# SCH_New_Project_2022-11-03.net
KiCad netlist of a schematic drawn in EasyEDA
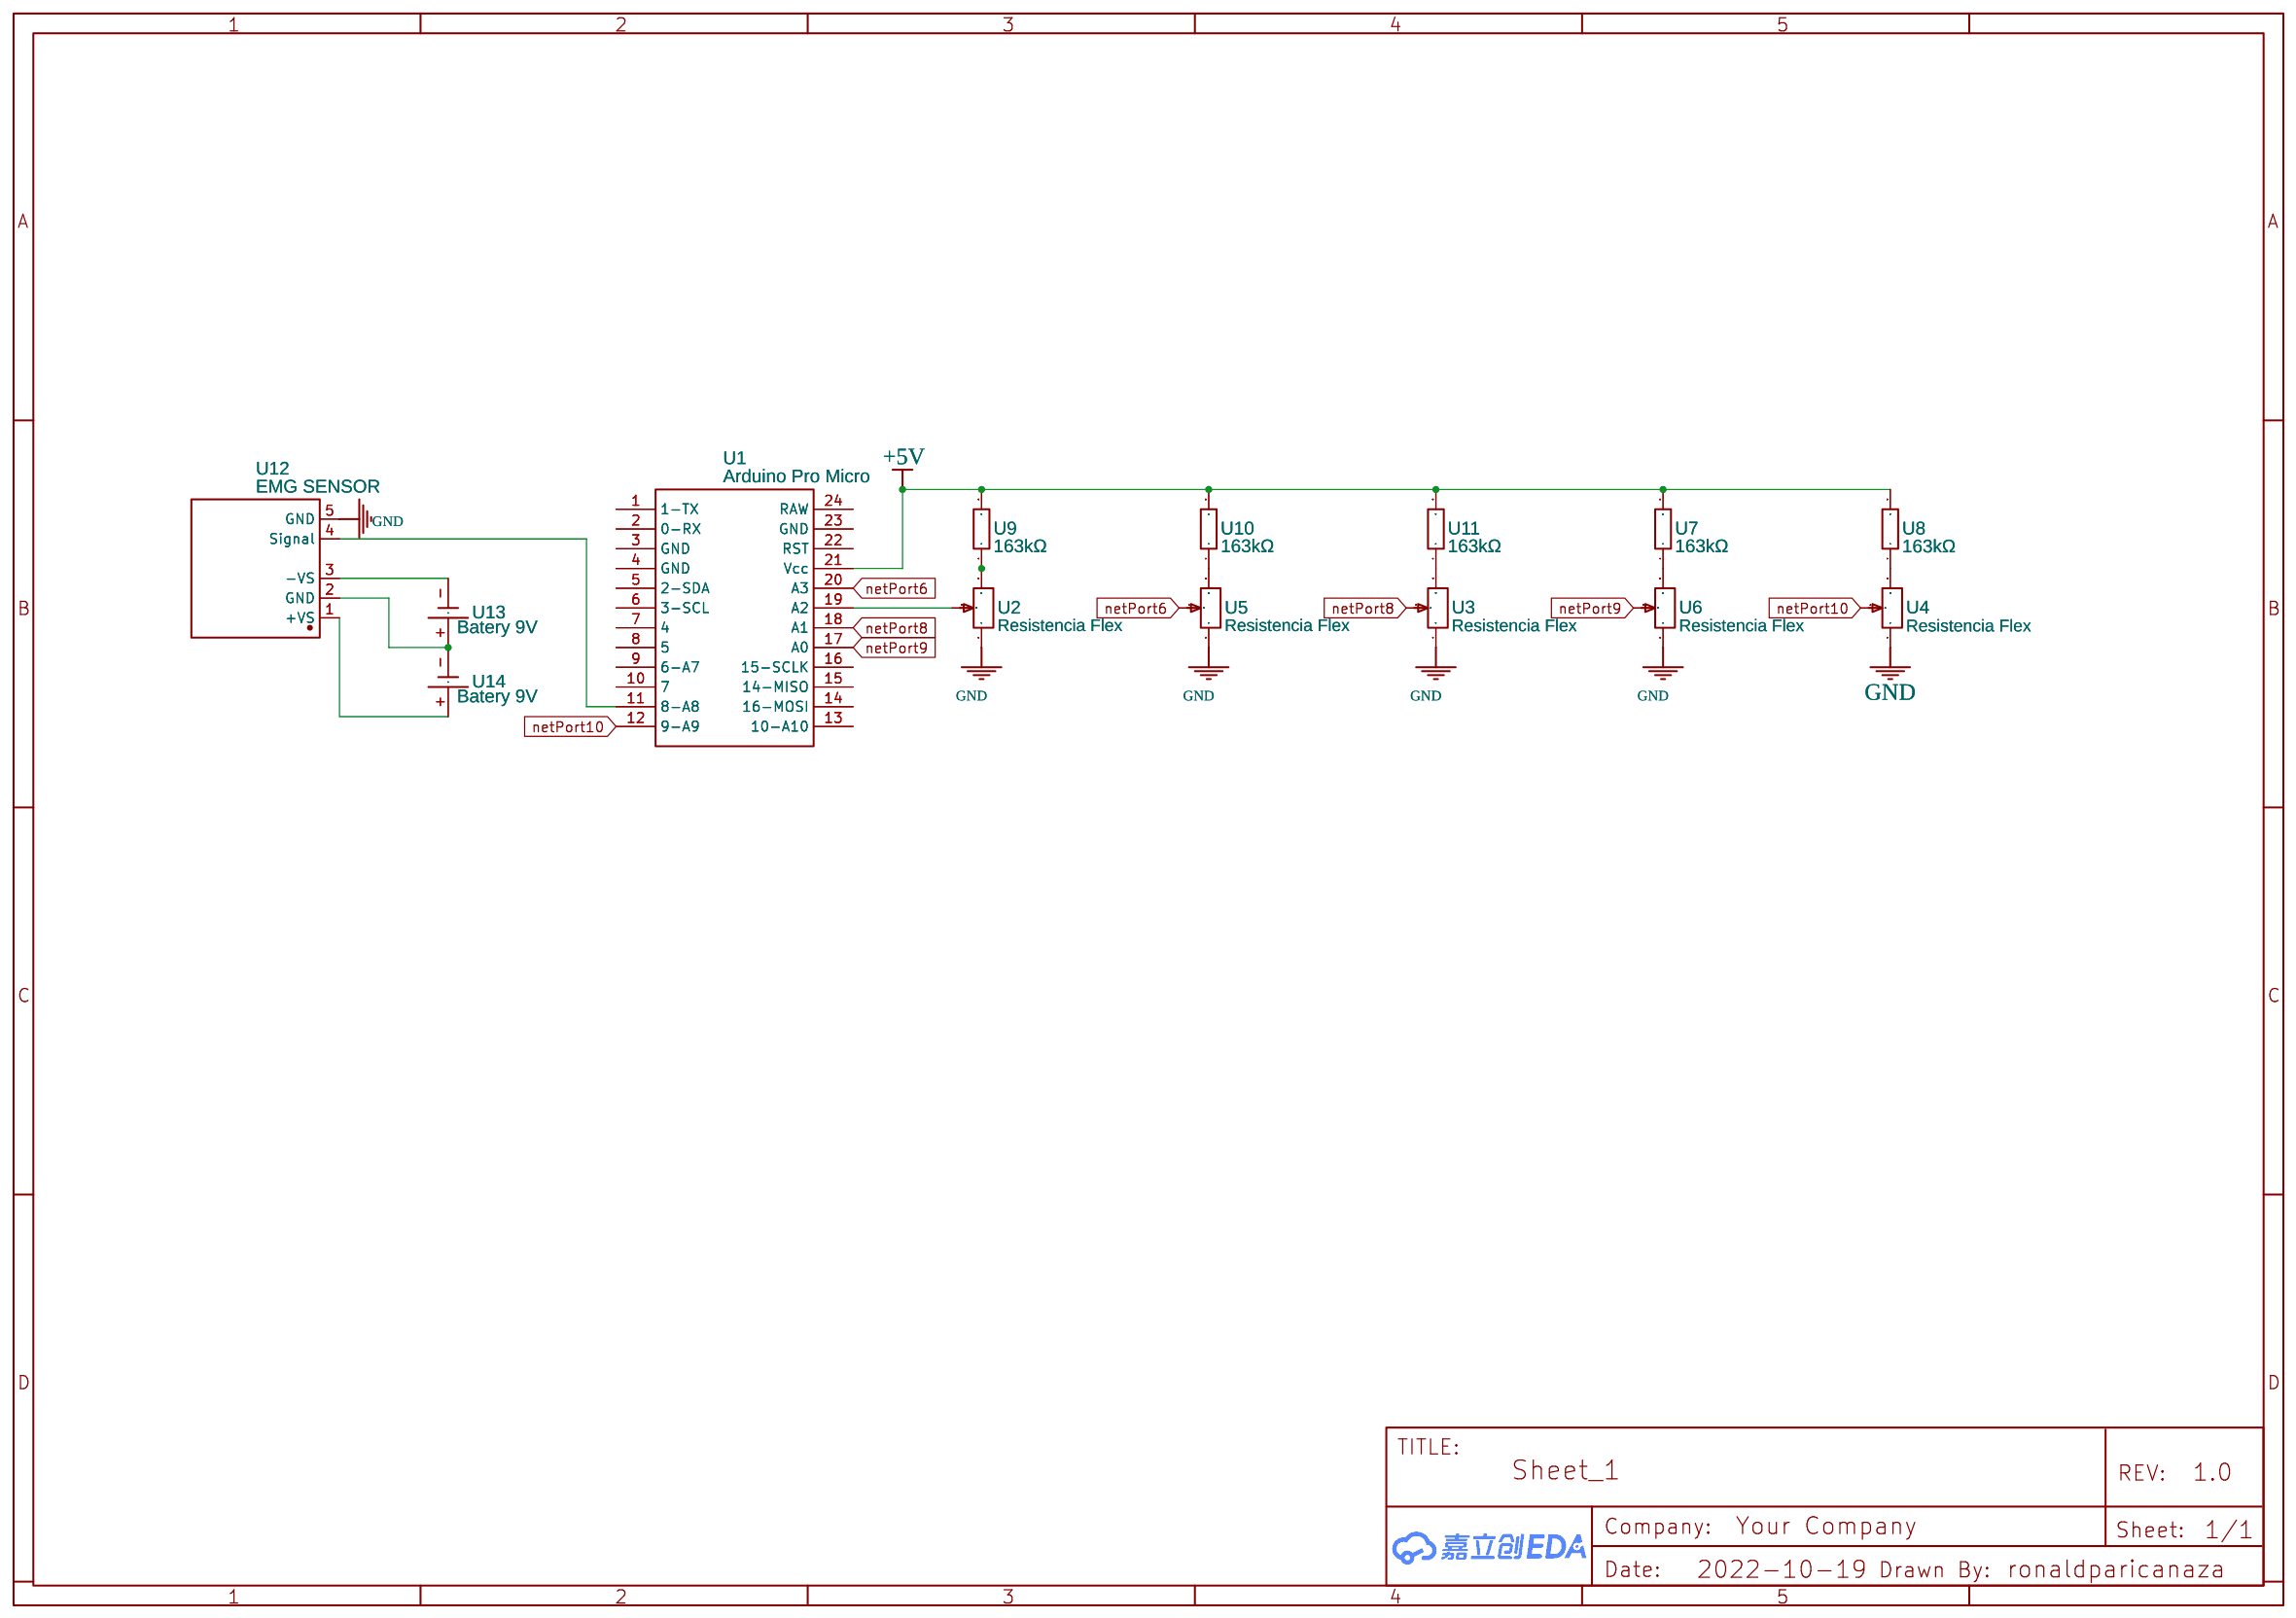
[diagram p0: schematic sheet]

(export (version "E")
  (design (tool "Eeschema 10.0.6"))
  (components
    (comp (ref "U1") (value "Arduino Pro Micro") (libsource (lib "") (part "Arduino Pro Micro")))
    (comp (ref "U2")
      (value "Resistencia Flex")
      (fields
        (field (name "BOM_Manufacturer Part") "3*3Potentiometer-10kΩ20%")
        (field (name "BOM_Supplier Part") "C9900010776")
      )
      (libsource (lib "") (part "3*3POTENTIOMETER-10KΩ20%"))
    )
    (comp (ref "U3")
      (value "Resistencia Flex")
      (fields
        (field (name "BOM_Manufacturer Part") "3*3Potentiometer-10kΩ20%")
        (field (name "BOM_Supplier Part") "C9900010776")
      )
      (libsource (lib "") (part "3*3POTENTIOMETER-10KΩ20%"))
    )
    (comp (ref "U4")
      (value "Resistencia Flex")
      (fields
        (field (name "BOM_Manufacturer Part") "3*3Potentiometer-10kΩ20%")
        (field (name "BOM_Supplier Part") "C9900010776")
      )
      (libsource (lib "") (part "3*3POTENTIOMETER-10KΩ20%"))
    )
    (comp (ref "U5")
      (value "Resistencia Flex")
      (fields
        (field (name "BOM_Manufacturer Part") "3*3Potentiometer-10kΩ20%")
        (field (name "BOM_Supplier Part") "C9900010776")
      )
      (libsource (lib "") (part "3*3POTENTIOMETER-10KΩ20%"))
    )
    (comp (ref "U6")
      (value "Resistencia Flex")
      (fields
        (field (name "BOM_Manufacturer Part") "3*3Potentiometer-10kΩ20%")
        (field (name "BOM_Supplier Part") "C9900010776")
      )
      (libsource (lib "") (part "3*3POTENTIOMETER-10KΩ20%"))
    )
    (comp (ref "U7")
      (value "163kΩ")
      (fields
        (field (name "BOM_Manufacturer Part") "HPCR0402F475KK9")
        (field (name "BOM_Supplier Part") "C365017")
      )
      (libsource (lib "") (part "HPCR0402F475KK9"))
    )
    (comp (ref "U8")
      (value "163kΩ")
      (fields
        (field (name "BOM_Manufacturer Part") "HPCR0402F475KK9")
        (field (name "BOM_Supplier Part") "C365017")
      )
      (libsource (lib "") (part "HPCR0402F475KK9"))
    )
    (comp (ref "U9")
      (value "163kΩ")
      (fields
        (field (name "BOM_Manufacturer Part") "HPCR0402F475KK9")
        (field (name "BOM_Supplier Part") "C365017")
      )
      (libsource (lib "") (part "HPCR0402F475KK9"))
    )
    (comp (ref "U10")
      (value "163kΩ")
      (fields
        (field (name "BOM_Manufacturer Part") "HPCR0402F475KK9")
        (field (name "BOM_Supplier Part") "C365017")
      )
      (libsource (lib "") (part "HPCR0402F475KK9"))
    )
    (comp (ref "U11")
      (value "163kΩ")
      (fields
        (field (name "BOM_Manufacturer Part") "HPCR0402F475KK9")
        (field (name "BOM_Supplier Part") "C365017")
      )
      (libsource (lib "") (part "HPCR0402F475KK9"))
    )
    (comp (ref "U12") (value "EMG SENSOR") (libsource (lib "") (part "EMG SENSOR")))
    (comp (ref "U13") (value "Batery 9V") (libsource (lib "") (part "Batery")))
    (comp (ref "U14") (value "Batery 9V") (libsource (lib "") (part "Batery")))
  )
  (nets
    (net (code "1") (name "+5V") (class "Default")
      (node (ref "U1") (pin "21") (pinfunction "Vcc_21") (pintype "unspecified"))
      (node (ref "U10") (pin "2") (pinfunction "2_2") (pintype "unspecified"))
      (node (ref "U11") (pin "2") (pinfunction "2_2") (pintype "unspecified"))
      (node (ref "U7") (pin "2") (pinfunction "2_2") (pintype "unspecified"))
      (node (ref "U8") (pin "2") (pinfunction "2_2") (pintype "unspecified"))
      (node (ref "U9") (pin "2") (pinfunction "2_2") (pintype "unspecified"))
    )
    (net (code "2") (name "GND") (class "Default")
      (node (ref "U12") (pin "5") (pinfunction "GND_5") (pintype "unspecified"))
      (node (ref "U2") (pin "1") (pinfunction "1_1") (pintype "input"))
      (node (ref "U3") (pin "1") (pinfunction "1_1") (pintype "input"))
      (node (ref "U4") (pin "1") (pinfunction "1_1") (pintype "input"))
      (node (ref "U5") (pin "1") (pinfunction "1_1") (pintype "input"))
      (node (ref "U6") (pin "1") (pinfunction "1_1") (pintype "input"))
    )
    (net (code "3") (name "Net-(U1-8-A8)") (class "Default")
      (node (ref "U1") (pin "11") (pinfunction "8-A8_11") (pintype "unspecified"))
      (node (ref "U12") (pin "4") (pinfunction "Signal_4") (pintype "unspecified"))
    )
    (net (code "4") (name "Net-(U1-A2)") (class "Default")
      (node (ref "U1") (pin "19") (pinfunction "A2_19") (pintype "unspecified"))
      (node (ref "U2") (pin "2") (pinfunction "2_2") (pintype "input"))
    )
    (net (code "5") (name "Net-(U2-Pad3)") (class "Default")
      (node (ref "U2") (pin "3") (pinfunction "3_3") (pintype "input"))
      (node (ref "U9") (pin "1") (pinfunction "1_1") (pintype "unspecified"))
    )
    (net (code "6") (name "Net-(U4-Pad3)") (class "Default")
      (node (ref "U4") (pin "3") (pinfunction "3_3") (pintype "input"))
      (node (ref "U8") (pin "1") (pinfunction "1_1") (pintype "unspecified"))
    )
    (net (code "7") (name "Net-(U6-Pad3)") (class "Default")
      (node (ref "U6") (pin "3") (pinfunction "3_3") (pintype "input"))
      (node (ref "U7") (pin "1") (pinfunction "1_1") (pintype "unspecified"))
    )
    (net (code "8") (name "Net-(U10-Pad1)") (class "Default")
      (node (ref "U10") (pin "1") (pinfunction "1_1") (pintype "unspecified"))
      (node (ref "U5") (pin "3") (pinfunction "3_3") (pintype "input"))
    )
    (net (code "9") (name "Net-(U11-Pad1)") (class "Default")
      (node (ref "U11") (pin "1") (pinfunction "1_1") (pintype "unspecified"))
      (node (ref "U3") (pin "3") (pinfunction "3_3") (pintype "input"))
    )
    (net (code "10") (name "Net-(U12-+VS)") (class "Default")
      (node (ref "U12") (pin "1") (pinfunction "+VS_1") (pintype "unspecified"))
      (node (ref "U14") (pin "+") (pinfunction "+_+") (pintype "unspecified"))
    )
    (net (code "11") (name "Net-(U12--VS)") (class "Default")
      (node (ref "U12") (pin "3") (pinfunction "-VS_3") (pintype "unspecified"))
      (node (ref "U13") (pin "-") (pinfunction "-_-") (pintype "unspecified"))
    )
    (net (code "12") (name "Net-(U12-GND-Pad2)") (class "Default")
      (node (ref "U12") (pin "2") (pinfunction "GND_2") (pintype "unspecified"))
      (node (ref "U13") (pin "+") (pinfunction "+_+") (pintype "unspecified"))
      (node (ref "U14") (pin "-") (pinfunction "-_-") (pintype "unspecified"))
    )
    (net (code "13") (name "netPort6") (class "Default")
      (node (ref "U1") (pin "20") (pinfunction "A3_20") (pintype "unspecified"))
      (node (ref "U5") (pin "2") (pinfunction "2_2") (pintype "input"))
    )
    (net (code "14") (name "netPort8") (class "Default")
      (node (ref "U1") (pin "18") (pinfunction "A1_18") (pintype "unspecified"))
      (node (ref "U3") (pin "2") (pinfunction "2_2") (pintype "input"))
    )
    (net (code "15") (name "netPort9") (class "Default")
      (node (ref "U1") (pin "17") (pinfunction "A0_17") (pintype "unspecified"))
      (node (ref "U6") (pin "2") (pinfunction "2_2") (pintype "input"))
    )
    (net (code "16") (name "netPort10") (class "Default")
      (node (ref "U1") (pin "12") (pinfunction "9-A9_12") (pintype "unspecified"))
      (node (ref "U4") (pin "2") (pinfunction "2_2") (pintype "input"))
    )
    (net (code "17") (name "unconnected-(U1-0-RX-Pad2)") (class "Default")
      (node (ref "U1") (pin "2") (pinfunction "0-RX_2") (pintype "unspecified"))
    )
    (net (code "18") (name "unconnected-(U1-1-TX-Pad1)") (class "Default")
      (node (ref "U1") (pin "1") (pinfunction "1-TX_1") (pintype "unspecified"))
    )
    (net (code "19") (name "unconnected-(U1-2-SDA-Pad5)") (class "Default")
      (node (ref "U1") (pin "5") (pinfunction "2-SDA_5") (pintype "unspecified"))
    )
    (net (code "20") (name "unconnected-(U1-3-SCL-Pad6)") (class "Default")
      (node (ref "U1") (pin "6") (pinfunction "3-SCL_6") (pintype "unspecified"))
    )
    (net (code "21") (name "unconnected-(U1-4-Pad7)") (class "Default")
      (node (ref "U1") (pin "7") (pinfunction "4_7") (pintype "unspecified"))
    )
    (net (code "22") (name "unconnected-(U1-5-Pad8)") (class "Default")
      (node (ref "U1") (pin "8") (pinfunction "5_8") (pintype "unspecified"))
    )
    (net (code "23") (name "unconnected-(U1-6-A7-Pad9)") (class "Default")
      (node (ref "U1") (pin "9") (pinfunction "6-A7_9") (pintype "unspecified"))
    )
    (net (code "24") (name "unconnected-(U1-7-Pad10)") (class "Default")
      (node (ref "U1") (pin "10") (pinfunction "7_10") (pintype "unspecified"))
    )
    (net (code "25") (name "unconnected-(U1-10-A10-Pad13)") (class "Default")
      (node (ref "U1") (pin "13") (pinfunction "10-A10_13") (pintype "unspecified"))
    )
    (net (code "26") (name "unconnected-(U1-14-MISO-Pad15)") (class "Default")
      (node (ref "U1") (pin "15") (pinfunction "14-MISO_15") (pintype "unspecified"))
    )
    (net (code "27") (name "unconnected-(U1-15-SCLK-Pad16)") (class "Default")
      (node (ref "U1") (pin "16") (pinfunction "15-SCLK_16") (pintype "unspecified"))
    )
    (net (code "28") (name "unconnected-(U1-16-MOSI-Pad14)") (class "Default")
      (node (ref "U1") (pin "14") (pinfunction "16-MOSI_14") (pintype "unspecified"))
    )
    (net (code "29") (name "unconnected-(U1-GND-Pad3)") (class "Default")
      (node (ref "U1") (pin "3") (pinfunction "GND_3") (pintype "unspecified"))
    )
    (net (code "30") (name "unconnected-(U1-GND-Pad4)") (class "Default")
      (node (ref "U1") (pin "4") (pinfunction "GND_4") (pintype "unspecified"))
    )
    (net (code "31") (name "unconnected-(U1-GND-Pad23)") (class "Default")
      (node (ref "U1") (pin "23") (pinfunction "GND_23") (pintype "unspecified"))
    )
    (net (code "32") (name "unconnected-(U1-RAW-Pad24)") (class "Default")
      (node (ref "U1") (pin "24") (pinfunction "RAW_24") (pintype "unspecified"))
    )
    (net (code "33") (name "unconnected-(U1-RST-Pad22)") (class "Default")
      (node (ref "U1") (pin "22") (pinfunction "RST_22") (pintype "unspecified"))
    )
  )
)
